# dawa_v4_0.net
KiCad netlist of a schematic drawn in EAGLE
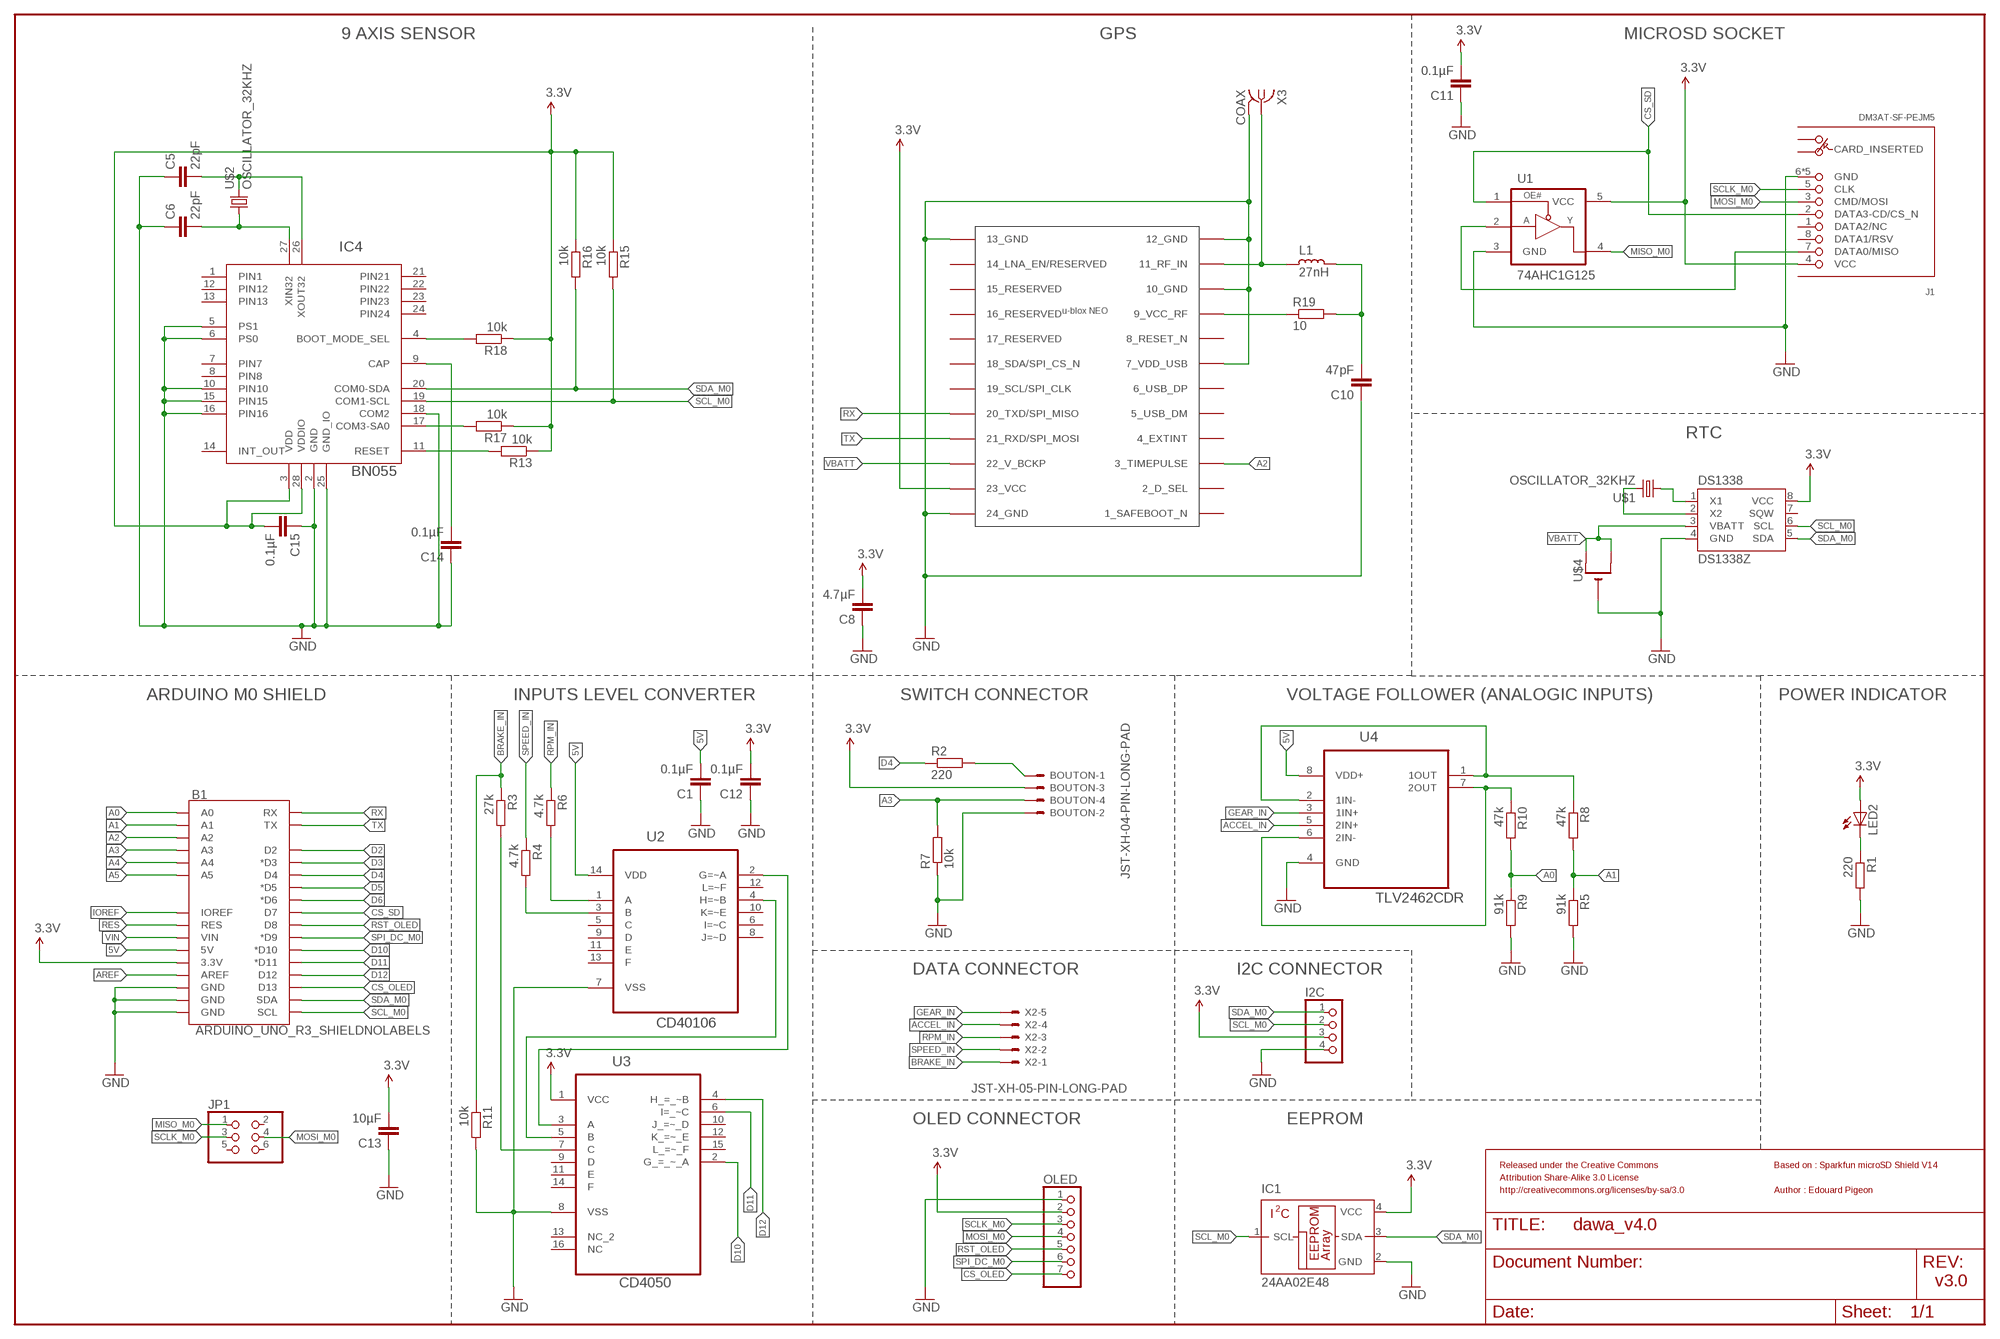
[diagram p0: schematic, sheet 1]

(export (version "E")
  (design (tool "Eeschema 10.0.6"))
  (components
    (comp (ref "B1")
      (value "ARDUINO_UNO_R3_SHIELDNOLABELS")
      (footprint "eagle-import:UNO_R3_SHIELD_NOLABELS")
      (libsource (lib "eagle-import") (part "ARDUINO_UNO_R3_SHIELDNOLABELS"))
    )
    (comp (ref "BOUTON")
      (value "JST-XH-04-PIN-LONG-PAD")
      (footprint "eagle-import:JST-XH-04-PACKAGE-LONG-PAD")
      (libsource (lib "eagle-import") (part "JST-XH-04-PIN-LONG-PAD"))
    )
    (comp (ref "C1")
      (value "0.1µF")
      (footprint "eagle-import:C0603")
      (libsource (lib "eagle-import") (part "C-EUC0603"))
    )
    (comp (ref "C5")
      (value "22pF")
      (footprint "eagle-import:C0603")
      (libsource (lib "eagle-import") (part "C-EUC0603"))
    )
    (comp (ref "C6")
      (value "22pF")
      (footprint "eagle-import:C0603")
      (libsource (lib "eagle-import") (part "C-EUC0603"))
    )
    (comp (ref "C8")
      (value "4.7µF")
      (footprint "eagle-import:C0603")
      (libsource (lib "eagle-import") (part "C-EUC0603"))
    )
    (comp (ref "C10")
      (value "47pF")
      (footprint "eagle-import:C0603")
      (libsource (lib "eagle-import") (part "C-EUC0603"))
    )
    (comp (ref "C11")
      (value "0.1µF")
      (footprint "eagle-import:C0603")
      (libsource (lib "eagle-import") (part "C-EUC0603"))
    )
    (comp (ref "C12")
      (value "0.1µF")
      (footprint "eagle-import:C0603")
      (libsource (lib "eagle-import") (part "C-EUC0603"))
    )
    (comp (ref "C13")
      (value "10µF")
      (footprint "eagle-import:C0603")
      (libsource (lib "eagle-import") (part "C-EUC0603"))
    )
    (comp (ref "C14")
      (value "0.1µF")
      (footprint "eagle-import:C0603")
      (libsource (lib "eagle-import") (part "C-EUC0603"))
    )
    (comp (ref "C15")
      (value "0.1µF")
      (footprint "eagle-import:C0603")
      (libsource (lib "eagle-import") (part "C-EUC0603"))
    )
    (comp (ref "DS1338")
      (value "DS1338Z")
      (footprint "eagle-import:SO08")
      (libsource (lib "eagle-import") (part "DS1338Z"))
    )
    (comp (ref "I2C")
      (value "PINHD-1X4")
      (footprint "eagle-import:1X04")
      (libsource (lib "eagle-import") (part "PINHD-1X4"))
    )
    (comp (ref "IC1")
      (value "24AA02E48")
      (footprint "eagle-import:SOT23-5L")
      (fields (field (name "MF") "MICROCHIP") (field (name "MPN") "24AA00T-I/OTG"))
      (libsource (lib "eagle-import") (part "2400OTAA"))
    )
    (comp (ref "IC4")
      (value "BN055")
      (footprint "eagle-import:LGA-28_3.80X5.20_0.5")
      (fields (field (name "PART_NUMBER") "BNO055"))
      (libsource (lib "eagle-import") (part "1658_BNO055"))
    )
    (comp (ref "J1")
      (value "DM3AT-SF-PEJM5")
      (footprint "eagle-import:DM3AT-SF-PEJM5")
      (libsource (lib "eagle-import") (part "DM3AT-SF-PEJM5"))
    )
    (comp (ref "JP1")
      (value "PINHD-2X3")
      (footprint "eagle-import:2X03")
      (libsource (lib "eagle-import") (part "PINHD-2X3"))
    )
    (comp (ref "L1")
      (value "27nH")
      (footprint "eagle-import:L0603")
      (libsource (lib "eagle-import") (part "L_0603"))
    )
    (comp (ref "LED2")
      (value "LEDCHIPLED_1206")
      (footprint "eagle-import:CHIPLED_1206")
      (libsource (lib "eagle-import") (part "LEDCHIPLED_1206"))
    )
    (comp (ref "OLED")
      (value "PINHD-1X7")
      (footprint "eagle-import:1X07")
      (libsource (lib "eagle-import") (part "PINHD-1X7"))
    )
    (comp (ref "R1")
      (value "220")
      (footprint "eagle-import:R0603")
      (libsource (lib "eagle-import") (part "R-EU_R0603"))
    )
    (comp (ref "R2")
      (value "220")
      (footprint "eagle-import:R0603")
      (libsource (lib "eagle-import") (part "R-EU_R0603"))
    )
    (comp (ref "R3")
      (value "27k")
      (footprint "eagle-import:R0603")
      (libsource (lib "eagle-import") (part "R-EU_R0603"))
    )
    (comp (ref "R4")
      (value "4.7k")
      (footprint "eagle-import:R0603")
      (libsource (lib "eagle-import") (part "R-EU_R0603"))
    )
    (comp (ref "R5")
      (value "91k")
      (footprint "eagle-import:R0603")
      (libsource (lib "eagle-import") (part "R-EU_R0603"))
    )
    (comp (ref "R6")
      (value "4.7k")
      (footprint "eagle-import:R0603")
      (libsource (lib "eagle-import") (part "R-EU_R0603"))
    )
    (comp (ref "R7")
      (value "10k")
      (footprint "eagle-import:R0603")
      (libsource (lib "eagle-import") (part "R-EU_R0603"))
    )
    (comp (ref "R8")
      (value "47k")
      (footprint "eagle-import:R0603")
      (libsource (lib "eagle-import") (part "R-EU_R0603"))
    )
    (comp (ref "R9")
      (value "91k")
      (footprint "eagle-import:R0603")
      (libsource (lib "eagle-import") (part "R-EU_R0603"))
    )
    (comp (ref "R10")
      (value "47k")
      (footprint "eagle-import:R0603")
      (libsource (lib "eagle-import") (part "R-EU_R0603"))
    )
    (comp (ref "R11")
      (value "10k")
      (footprint "eagle-import:R0603")
      (libsource (lib "eagle-import") (part "R-EU_R0603"))
    )
    (comp (ref "R13")
      (value "10k")
      (footprint "eagle-import:R0603")
      (libsource (lib "eagle-import") (part "R-EU_R0603"))
    )
    (comp (ref "R15")
      (value "10k")
      (footprint "eagle-import:R0603")
      (libsource (lib "eagle-import") (part "R-EU_R0603"))
    )
    (comp (ref "R16")
      (value "10k")
      (footprint "eagle-import:R0603")
      (libsource (lib "eagle-import") (part "R-EU_R0603"))
    )
    (comp (ref "R17")
      (value "10k")
      (footprint "eagle-import:R0603")
      (libsource (lib "eagle-import") (part "R-EU_R0603"))
    )
    (comp (ref "R18")
      (value "10k")
      (footprint "eagle-import:R0603")
      (libsource (lib "eagle-import") (part "R-EU_R0603"))
    )
    (comp (ref "R19")
      (value "10")
      (footprint "eagle-import:M1206")
      (libsource (lib "eagle-import") (part "R-EU_M1206"))
    )
    (comp (ref "U$1")
      (value "OSCILLATOR_32KHZ")
      (footprint "eagle-import:OSCILLATOR_SMD")
      (libsource (lib "eagle-import") (part "OSCILLATOR_32KHZ"))
    )
    (comp (ref "U$2")
      (value "OSCILLATOR_32KHZ")
      (footprint "eagle-import:OSCILLATOR_SMD")
      (libsource (lib "eagle-import") (part "OSCILLATOR_32KHZ"))
    )
    (comp (ref "U$3")
      (value "NEO-M8")
      (footprint "eagle-import:NEO-M8")
      (libsource (lib "eagle-import") (part "NEO-M8"))
    )
    (comp (ref "U$4")
      (value "CR1220SMT")
      (footprint "eagle-import:CR1220-SMD")
      (libsource (lib "eagle-import") (part "CR1220SMT"))
    )
    (comp (ref "U1")
      (value "74AHC1G125")
      (footprint "eagle-import:SOT23-5")
      (libsource (lib "eagle-import") (part "74AHC1G125DBV"))
    )
    (comp (ref "U2")
      (value "CD40106")
      (footprint "eagle-import:SOP65P640X120-14N")
      (fields (field (name "MPN") "CD40106BPW"))
      (libsource (lib "eagle-import") (part "CD40106BPW"))
    )
    (comp (ref "U3")
      (value "CD4050")
      (footprint "eagle-import:SOP65P640X120-16N")
      (fields (field (name "MPN") "CD4049UBPW"))
      (libsource (lib "eagle-import") (part "CD4049UBPW"))
    )
    (comp (ref "U4")
      (value "TLV2462CDR")
      (footprint "eagle-import:SOIC127P600X175-8N")
      (libsource (lib "eagle-import") (part "TLV2462CDR"))
    )
    (comp (ref "X2")
      (value "JST-XH-05-PIN-LONG-PAD")
      (footprint "eagle-import:JST-XH-05-PACKAGE-LONG-PAD")
      (libsource (lib "eagle-import") (part "JST-XH-05-PIN-LONG-PAD"))
    )
    (comp (ref "X3")
      (value "COAX")
      (footprint "eagle-import:MMCX-J-P-X-ST-EM1-MKT")
      (libsource (lib "eagle-import") (part "COAX"))
    )
  )
  (nets
    (net (code "1") (name "3.3V") (class "Default")
      (node (ref "B1") (pin "3.3V") (pinfunction "3.3V_3.3V") (pintype "bidirectional"))
      (node (ref "BOUTON") (pin "3") (pinfunction "S_3") (pintype "passive"))
      (node (ref "C11") (pin "2") (pinfunction "2_2") (pintype "passive"))
      (node (ref "C12") (pin "2") (pinfunction "2_2") (pintype "passive"))
      (node (ref "C13") (pin "2") (pinfunction "2_2") (pintype "passive"))
      (node (ref "C15") (pin "2") (pinfunction "2_2") (pintype "passive"))
      (node (ref "C8") (pin "2") (pinfunction "2_2") (pintype "passive"))
      (node (ref "DS1338") (pin "8") (pinfunction "VCC_8") (pintype "bidirectional"))
      (node (ref "I2C") (pin "3") (pinfunction "3_3") (pintype "passive"))
      (node (ref "IC1") (pin "4") (pinfunction "VCC_4") (pintype "power_in"))
      (node (ref "IC4") (pin "28") (pinfunction "VDDIO_28") (pintype "power_in"))
      (node (ref "IC4") (pin "3") (pinfunction "VDD_3") (pintype "power_in"))
      (node (ref "J1") (pin "4") (pinfunction "VCC_4") (pintype "bidirectional"))
      (node (ref "LED2") (pin "A") (pinfunction "A_A") (pintype "passive"))
      (node (ref "OLED") (pin "2") (pinfunction "2_2") (pintype "passive"))
      (node (ref "R13") (pin "1") (pinfunction "1_1") (pintype "passive"))
      (node (ref "R15") (pin "1") (pinfunction "1_1") (pintype "passive"))
      (node (ref "R16") (pin "1") (pinfunction "1_1") (pintype "passive"))
      (node (ref "R17") (pin "1") (pinfunction "1_1") (pintype "passive"))
      (node (ref "R18") (pin "1") (pinfunction "1_1") (pintype "passive"))
      (node (ref "U$3") (pin "23") (pinfunction "23_VCC_23") (pintype "bidirectional"))
      (node (ref "U1") (pin "5") (pinfunction "VCC_5") (pintype "power_in"))
      (node (ref "U3") (pin "1") (pinfunction "VCC_1") (pintype "power_in"))
    )
    (net (code "2") (name "5V") (class "Default")
      (node (ref "B1") (pin "5V") (pinfunction "5V_5V") (pintype "bidirectional"))
      (node (ref "C1") (pin "2") (pinfunction "2_2") (pintype "passive"))
      (node (ref "U2") (pin "14") (pinfunction "VDD_14") (pintype "power_in"))
      (node (ref "U4") (pin "8") (pinfunction "VDD+_8") (pintype "power_in"))
    )
    (net (code "3") (name "A0") (class "Default")
      (node (ref "B1") (pin "A0") (pinfunction "A0_A0") (pintype "bidirectional"))
      (node (ref "R10") (pin "2") (pinfunction "2_2") (pintype "passive"))
      (node (ref "R9") (pin "1") (pinfunction "1_1") (pintype "passive"))
    )
    (net (code "4") (name "A1") (class "Default")
      (node (ref "B1") (pin "A1") (pinfunction "A1_A1") (pintype "bidirectional"))
      (node (ref "R5") (pin "1") (pinfunction "1_1") (pintype "passive"))
      (node (ref "R8") (pin "2") (pinfunction "2_2") (pintype "passive"))
    )
    (net (code "5") (name "A2") (class "Default")
      (node (ref "B1") (pin "A2") (pinfunction "A2_A2") (pintype "bidirectional"))
      (node (ref "U$3") (pin "3") (pinfunction "3_TIMEPULSE_3") (pintype "bidirectional"))
    )
    (net (code "6") (name "A3") (class "Default")
      (node (ref "B1") (pin "A3") (pinfunction "A3_A3") (pintype "bidirectional"))
      (node (ref "BOUTON") (pin "4") (pinfunction "S_4") (pintype "passive"))
      (node (ref "R7") (pin "2") (pinfunction "2_2") (pintype "passive"))
    )
    (net (code "7") (name "A4") (class "Default")
      (node (ref "B1") (pin "A4") (pinfunction "A4_A4") (pintype "bidirectional"))
    )
    (net (code "8") (name "A5") (class "Default")
      (node (ref "B1") (pin "A5") (pinfunction "A5_A5") (pintype "bidirectional"))
    )
    (net (code "9") (name "ACCEL_IN") (class "Default")
      (node (ref "U4") (pin "5") (pinfunction "2IN+_5") (pintype "input"))
      (node (ref "X2") (pin "4") (pinfunction "S_4") (pintype "passive"))
    )
    (net (code "10") (name "AREF") (class "Default")
      (node (ref "B1") (pin "AREF") (pinfunction "AREF_AREF") (pintype "bidirectional"))
    )
    (net (code "11") (name "BRAKE_IN") (class "Default")
      (node (ref "R11") (pin "1") (pinfunction "1_1") (pintype "passive"))
      (node (ref "R3") (pin "1") (pinfunction "1_1") (pintype "passive"))
      (node (ref "X2") (pin "1") (pinfunction "S_1") (pintype "passive"))
    )
    (net (code "12") (name "CS_OLED") (class "Default")
      (node (ref "B1") (pin "D13") (pinfunction "D13_D13") (pintype "bidirectional"))
      (node (ref "OLED") (pin "7") (pinfunction "7_7") (pintype "passive"))
    )
    (net (code "13") (name "CS_SD") (class "Default")
      (node (ref "B1") (pin "D7") (pinfunction "D7_D7") (pintype "bidirectional"))
      (node (ref "J1") (pin "2") (pinfunction "DATA3-CD/CS_N_2") (pintype "bidirectional"))
      (node (ref "U1") (pin "1") (pinfunction "OE#_1") (pintype "input"))
    )
    (net (code "14") (name "D2") (class "Default")
      (node (ref "B1") (pin "D2") (pinfunction "D2_D2") (pintype "bidirectional"))
    )
    (net (code "15") (name "D3") (class "Default")
      (node (ref "B1") (pin "D3") (pinfunction "*D3_D3") (pintype "bidirectional"))
    )
    (net (code "16") (name "D4") (class "Default")
      (node (ref "B1") (pin "D4") (pinfunction "D4_D4") (pintype "bidirectional"))
      (node (ref "R2") (pin "1") (pinfunction "1_1") (pintype "passive"))
    )
    (net (code "17") (name "D5") (class "Default")
      (node (ref "B1") (pin "D5") (pinfunction "*D5_D5") (pintype "bidirectional"))
    )
    (net (code "18") (name "D6") (class "Default")
      (node (ref "B1") (pin "D6") (pinfunction "*D6_D6") (pintype "bidirectional"))
    )
    (net (code "19") (name "D10") (class "Default")
      (node (ref "B1") (pin "D10") (pinfunction "*D10_D10") (pintype "bidirectional"))
      (node (ref "U3") (pin "2") (pinfunction "G_=_~{_A}_2") (pintype "output"))
    )
    (net (code "20") (name "D11") (class "Default")
      (node (ref "B1") (pin "D11") (pinfunction "*D11_D11") (pintype "bidirectional"))
      (node (ref "U3") (pin "6") (pinfunction "I=_~{C}_6") (pintype "output"))
    )
    (net (code "21") (name "D12") (class "Default")
      (node (ref "B1") (pin "D12") (pinfunction "D12_D12") (pintype "bidirectional"))
      (node (ref "U3") (pin "4") (pinfunction "H_=_~{B}_4") (pintype "output"))
    )
    (net (code "22") (name "GEAR_IN") (class "Default")
      (node (ref "U4") (pin "3") (pinfunction "1IN+_3") (pintype "input"))
      (node (ref "X2") (pin "5") (pinfunction "S_5") (pintype "passive"))
    )
    (net (code "23") (name "GND") (class "Default")
      (node (ref "B1") (pin "GND@0") (pinfunction "GND_GND@0") (pintype "bidirectional"))
      (node (ref "B1") (pin "GND@1") (pinfunction "GND_GND@1") (pintype "bidirectional"))
      (node (ref "B1") (pin "GND@2") (pinfunction "GND_GND@2") (pintype "bidirectional"))
      (node (ref "BOUTON") (pin "2") (pinfunction "S_2") (pintype "passive"))
      (node (ref "C1") (pin "1") (pinfunction "1_1") (pintype "passive"))
      (node (ref "C10") (pin "1") (pinfunction "1_1") (pintype "passive"))
      (node (ref "C11") (pin "1") (pinfunction "1_1") (pintype "passive"))
      (node (ref "C12") (pin "1") (pinfunction "1_1") (pintype "passive"))
      (node (ref "C13") (pin "1") (pinfunction "1_1") (pintype "passive"))
      (node (ref "C14") (pin "1") (pinfunction "1_1") (pintype "passive"))
      (node (ref "C15") (pin "1") (pinfunction "1_1") (pintype "passive"))
      (node (ref "C5") (pin "1") (pinfunction "1_1") (pintype "passive"))
      (node (ref "C6") (pin "1") (pinfunction "1_1") (pintype "passive"))
      (node (ref "C8") (pin "1") (pinfunction "1_1") (pintype "passive"))
      (node (ref "DS1338") (pin "4") (pinfunction "GND_4") (pintype "bidirectional"))
      (node (ref "I2C") (pin "4") (pinfunction "4_4") (pintype "passive"))
      (node (ref "IC1") (pin "2") (pinfunction "GND_2") (pintype "power_in"))
      (node (ref "IC4") (pin "10") (pinfunction "PIN10_10") (pintype "passive"))
      (node (ref "IC4") (pin "15") (pinfunction "PIN15_15") (pintype "passive"))
      (node (ref "IC4") (pin "16") (pinfunction "PIN16_16") (pintype "passive"))
      (node (ref "IC4") (pin "18") (pinfunction "COM2_18") (pintype "bidirectional"))
      (node (ref "IC4") (pin "2") (pinfunction "GND_2") (pintype "power_in"))
      (node (ref "IC4") (pin "25") (pinfunction "GND_IO_25") (pintype "power_in"))
      (node (ref "IC4") (pin "5") (pinfunction "PS1_5") (pintype "input"))
      (node (ref "IC4") (pin "6") (pinfunction "PS0_6") (pintype "input"))
      (node (ref "J1") (pin "6") (pinfunction "GND_6") (pintype "bidirectional"))
      (node (ref "J1") (pin "MOUNT0") (pinfunction "GND_MOUNT0") (pintype "bidirectional"))
      (node (ref "J1") (pin "MOUNT1") (pinfunction "GND_MOUNT1") (pintype "bidirectional"))
      (node (ref "J1") (pin "MOUNT2") (pinfunction "GND_MOUNT2") (pintype "bidirectional"))
      (node (ref "J1") (pin "MOUNT3") (pinfunction "GND_MOUNT3") (pintype "bidirectional"))
      (node (ref "OLED") (pin "1") (pinfunction "1_1") (pintype "passive"))
      (node (ref "R1") (pin "2") (pinfunction "2_2") (pintype "passive"))
      (node (ref "R11") (pin "2") (pinfunction "2_2") (pintype "passive"))
      (node (ref "R5") (pin "2") (pinfunction "2_2") (pintype "passive"))
      (node (ref "R7") (pin "1") (pinfunction "1_1") (pintype "passive"))
      (node (ref "R9") (pin "2") (pinfunction "2_2") (pintype "passive"))
      (node (ref "U$3") (pin "10") (pinfunction "10_GND_10") (pintype "bidirectional"))
      (node (ref "U$3") (pin "12") (pinfunction "12_GND_12") (pintype "bidirectional"))
      (node (ref "U$3") (pin "13") (pinfunction "13_GND_13") (pintype "bidirectional"))
      (node (ref "U$3") (pin "24") (pinfunction "24_GND_24") (pintype "bidirectional"))
      (node (ref "U$3") (pin "7") (pinfunction "7_VDD_USB_7") (pintype "bidirectional"))
      (node (ref "U$4") (pin "-") (pinfunction "-_-") (pintype "passive"))
      (node (ref "U1") (pin "3") (pinfunction "GND_3") (pintype "power_in"))
      (node (ref "U2") (pin "7") (pinfunction "VSS_7") (pintype "power_in"))
      (node (ref "U3") (pin "8") (pinfunction "VSS_8") (pintype "power_in"))
      (node (ref "U4") (pin "4") (pinfunction "GND_4") (pintype "passive"))
      (node (ref "X3") (pin "2@1") (pinfunction "GND_2@1") (pintype "power_in"))
    )
    (net (code "24") (name "IOREF") (class "Default")
      (node (ref "B1") (pin "IOREF") (pinfunction "IOREF_IOREF") (pintype "bidirectional"))
    )
    (net (code "25") (name "MISO_M0") (class "Default")
      (node (ref "JP1") (pin "1") (pinfunction "1_1") (pintype "passive"))
      (node (ref "U1") (pin "4") (pinfunction "Y_4") (pintype "output"))
    )
    (net (code "26") (name "MOSI_M0") (class "Default")
      (node (ref "J1") (pin "3") (pinfunction "CMD/MOSI_3") (pintype "bidirectional"))
      (node (ref "JP1") (pin "4") (pinfunction "4_4") (pintype "passive"))
      (node (ref "OLED") (pin "4") (pinfunction "4_4") (pintype "passive"))
    )
    (net (code "27") (name "Net-(BOUTONA-S)") (class "Default")
      (node (ref "BOUTON") (pin "1") (pinfunction "S_1") (pintype "passive"))
      (node (ref "R2") (pin "2") (pinfunction "2_2") (pintype "passive"))
    )
    (net (code "28") (name "Net-(C10-Pad2)") (class "Default")
      (node (ref "C10") (pin "2") (pinfunction "2_2") (pintype "passive"))
      (node (ref "L1") (pin "1") (pinfunction "1_1") (pintype "passive"))
      (node (ref "R19") (pin "2") (pinfunction "2_2") (pintype "passive"))
    )
    (net (code "29") (name "Net-(DS1338-X1)") (class "Default")
      (node (ref "DS1338") (pin "1") (pinfunction "X1_1") (pintype "bidirectional"))
      (node (ref "U$1") (pin "1") (pinfunction "1_1") (pintype "passive"))
    )
    (net (code "30") (name "Net-(DS1338-X2)") (class "Default")
      (node (ref "DS1338") (pin "2") (pinfunction "X2_2") (pintype "bidirectional"))
      (node (ref "U$1") (pin "2") (pinfunction "2_2") (pintype "passive"))
    )
    (net (code "31") (name "Net-(IC4-BOOT_MODE_SEL)") (class "Default")
      (node (ref "IC4") (pin "4") (pinfunction "BOOT_MODE_SEL_4") (pintype "input"))
      (node (ref "R18") (pin "2") (pinfunction "2_2") (pintype "passive"))
    )
    (net (code "32") (name "Net-(IC4-CAP)") (class "Default")
      (node (ref "C14") (pin "2") (pinfunction "2_2") (pintype "passive"))
      (node (ref "IC4") (pin "9") (pinfunction "CAP_9") (pintype "tri_state"))
    )
    (net (code "33") (name "Net-(IC4-COM3-SA0)") (class "Default")
      (node (ref "IC4") (pin "17") (pinfunction "COM3-SA0_17") (pintype "bidirectional"))
      (node (ref "R17") (pin "2") (pinfunction "2_2") (pintype "passive"))
    )
    (net (code "34") (name "Net-(IC4-RESET)") (class "Default")
      (node (ref "IC4") (pin "11") (pinfunction "RESET_11") (pintype "input"))
      (node (ref "R13") (pin "2") (pinfunction "2_2") (pintype "passive"))
    )
    (net (code "35") (name "Net-(IC4-XIN32)") (class "Default")
      (node (ref "C6") (pin "2") (pinfunction "2_2") (pintype "passive"))
      (node (ref "IC4") (pin "27") (pinfunction "XIN32_27") (pintype "bidirectional"))
      (node (ref "U$2") (pin "1") (pinfunction "1_1") (pintype "passive"))
    )
    (net (code "36") (name "Net-(IC4-XOUT32)") (class "Default")
      (node (ref "C5") (pin "2") (pinfunction "2_2") (pintype "passive"))
      (node (ref "IC4") (pin "26") (pinfunction "XOUT32_26") (pintype "output"))
      (node (ref "U$2") (pin "2") (pinfunction "2_2") (pintype "passive"))
    )
    (net (code "37") (name "Net-(J1-DATA0{slash}MISO)") (class "Default")
      (node (ref "J1") (pin "7") (pinfunction "DATA0/MISO_7") (pintype "bidirectional"))
      (node (ref "U1") (pin "2") (pinfunction "A_2") (pintype "input"))
    )
    (net (code "38") (name "Net-(LED2-PadC)") (class "Default")
      (node (ref "LED2") (pin "C") (pinfunction "C_C") (pintype "passive"))
      (node (ref "R1") (pin "1") (pinfunction "1_1") (pintype "passive"))
    )
    (net (code "39") (name "Net-(U$3-9_VCC_RF)") (class "Default")
      (node (ref "R19") (pin "1") (pinfunction "1_1") (pintype "passive"))
      (node (ref "U$3") (pin "9") (pinfunction "9_VCC_RF_9") (pintype "bidirectional"))
    )
    (net (code "40") (name "Net-(U$3-11_RF_IN)") (class "Default")
      (node (ref "L1") (pin "2") (pinfunction "2_2") (pintype "passive"))
      (node (ref "U$3") (pin "11") (pinfunction "11_RF_IN_11") (pintype "bidirectional"))
      (node (ref "X3") (pin "1") (pinfunction "1_1") (pintype "passive"))
    )
    (net (code "41") (name "Net-(U2-A)") (class "Default")
      (node (ref "R6") (pin "2") (pinfunction "2_2") (pintype "passive"))
      (node (ref "U2") (pin "1") (pinfunction "A_1") (pintype "input"))
    )
    (net (code "42") (name "Net-(U2-B)") (class "Default")
      (node (ref "R4") (pin "2") (pinfunction "2_2") (pintype "passive"))
      (node (ref "U2") (pin "3") (pinfunction "B_3") (pintype "input"))
    )
    (net (code "43") (name "Net-(U2-G=~{A})") (class "Default")
      (node (ref "U2") (pin "2") (pinfunction "G=~{A}_2") (pintype "output"))
      (node (ref "U3") (pin "3") (pinfunction "A_3") (pintype "input"))
    )
    (net (code "44") (name "Net-(U2-H=~{B})") (class "Default")
      (node (ref "U2") (pin "4") (pinfunction "H=~{B}_4") (pintype "output"))
      (node (ref "U3") (pin "5") (pinfunction "B_5") (pintype "input"))
    )
    (net (code "45") (name "Net-(U3-C)") (class "Default")
      (node (ref "R3") (pin "2") (pinfunction "2_2") (pintype "passive"))
      (node (ref "U3") (pin "7") (pinfunction "C_7") (pintype "input"))
    )
    (net (code "46") (name "Net-(U4-1IN-)") (class "Default")
      (node (ref "R8") (pin "1") (pinfunction "1_1") (pintype "passive"))
      (node (ref "U4") (pin "1") (pinfunction "1OUT_1") (pintype "output"))
      (node (ref "U4") (pin "2") (pinfunction "1IN-_2") (pintype "input"))
    )
    (net (code "47") (name "Net-(U4-2IN-)") (class "Default")
      (node (ref "R10") (pin "1") (pinfunction "1_1") (pintype "passive"))
      (node (ref "U4") (pin "6") (pinfunction "2IN-_6") (pintype "input"))
      (node (ref "U4") (pin "7") (pinfunction "2OUT_7") (pintype "output"))
    )
    (net (code "48") (name "RES") (class "Default")
      (node (ref "B1") (pin "RES") (pinfunction "RES_RES") (pintype "bidirectional"))
    )
    (net (code "49") (name "RPM_IN") (class "Default")
      (node (ref "R6") (pin "1") (pinfunction "1_1") (pintype "passive"))
      (node (ref "X2") (pin "3") (pinfunction "S_3") (pintype "passive"))
    )
    (net (code "50") (name "RST_OLED") (class "Default")
      (node (ref "B1") (pin "D8") (pinfunction "D8_D8") (pintype "bidirectional"))
      (node (ref "OLED") (pin "5") (pinfunction "5_5") (pintype "passive"))
    )
    (net (code "51") (name "RX") (class "Default")
      (node (ref "B1") (pin "RX") (pinfunction "RX_RX") (pintype "bidirectional"))
      (node (ref "U$3") (pin "20") (pinfunction "20_TXD/SPI_MISO_20") (pintype "bidirectional"))
    )
    (net (code "52") (name "SCLK_M0") (class "Default")
      (node (ref "J1") (pin "5") (pinfunction "CLK_5") (pintype "bidirectional"))
      (node (ref "JP1") (pin "3") (pinfunction "3_3") (pintype "passive"))
      (node (ref "OLED") (pin "3") (pinfunction "3_3") (pintype "passive"))
    )
    (net (code "53") (name "SCL_M0") (class "Default")
      (node (ref "B1") (pin "SCL") (pinfunction "SCL_SCL") (pintype "bidirectional"))
      (node (ref "DS1338") (pin "6") (pinfunction "SCL_6") (pintype "bidirectional"))
      (node (ref "I2C") (pin "2") (pinfunction "2_2") (pintype "passive"))
      (node (ref "IC1") (pin "1") (pinfunction "SCL_1") (pintype "input"))
      (node (ref "IC4") (pin "19") (pinfunction "COM1-SCL_19") (pintype "bidirectional"))
      (node (ref "R15") (pin "2") (pinfunction "2_2") (pintype "passive"))
    )
    (net (code "54") (name "SDA_M0") (class "Default")
      (node (ref "B1") (pin "SDA") (pinfunction "SDA_SDA") (pintype "bidirectional"))
      (node (ref "DS1338") (pin "5") (pinfunction "SDA_5") (pintype "bidirectional"))
      (node (ref "I2C") (pin "1") (pinfunction "1_1") (pintype "passive"))
      (node (ref "IC1") (pin "3") (pinfunction "SDA_3") (pintype "bidirectional"))
      (node (ref "IC4") (pin "20") (pinfunction "COM0-SDA_20") (pintype "bidirectional"))
      (node (ref "R16") (pin "2") (pinfunction "2_2") (pintype "passive"))
    )
    (net (code "55") (name "SPEED_IN") (class "Default")
      (node (ref "R4") (pin "1") (pinfunction "1_1") (pintype "passive"))
      (node (ref "X2") (pin "2") (pinfunction "S_2") (pintype "passive"))
    )
    (net (code "56") (name "SPI_DC_M0") (class "Default")
      (node (ref "B1") (pin "D9") (pinfunction "*D9_D9") (pintype "bidirectional"))
      (node (ref "OLED") (pin "6") (pinfunction "6_6") (pintype "passive"))
    )
    (net (code "57") (name "TX") (class "Default")
      (node (ref "B1") (pin "TX") (pinfunction "TX_TX") (pintype "bidirectional"))
      (node (ref "U$3") (pin "21") (pinfunction "21_RXD/SPI_MOSI_21") (pintype "bidirectional"))
    )
    (net (code "58") (name "VBATT") (class "Default")
      (node (ref "DS1338") (pin "3") (pinfunction "VBATT_3") (pintype "bidirectional"))
      (node (ref "U$3") (pin "22") (pinfunction "22_V_BCKP_22") (pintype "bidirectional"))
      (node (ref "U$4") (pin "+$1") (pinfunction "+_+$1") (pintype "passive"))
      (node (ref "U$4") (pin "+$2") (pinfunction "+1_+$2") (pintype "passive"))
    )
    (net (code "59") (name "VIN") (class "Default")
      (node (ref "B1") (pin "VIN") (pinfunction "VIN_VIN") (pintype "bidirectional"))
    )
    (net (code "60") (name "unconnected-(DS1338-SQW-Pad7)") (class "Default")
      (node (ref "DS1338") (pin "7") (pinfunction "SQW_7") (pintype "bidirectional"))
    )
    (net (code "61") (name "unconnected-(IC4-INT_OUT-Pad14)") (class "Default")
      (node (ref "IC4") (pin "14") (pinfunction "INT_OUT_14") (pintype "output"))
    )
    (net (code "62") (name "unconnected-(IC4-PIN1-Pad1)") (class "Default")
      (node (ref "IC4") (pin "1") (pinfunction "PIN1_1") (pintype "no_connect"))
    )
    (net (code "63") (name "unconnected-(IC4-PIN7-Pad7)") (class "Default")
      (node (ref "IC4") (pin "7") (pinfunction "PIN7_7") (pintype "tri_state"))
    )
    (net (code "64") (name "unconnected-(IC4-PIN8-Pad8)") (class "Default")
      (node (ref "IC4") (pin "8") (pinfunction "PIN8_8") (pintype "tri_state"))
    )
    (net (code "65") (name "unconnected-(IC4-PIN12-Pad12)") (class "Default")
      (node (ref "IC4") (pin "12") (pinfunction "PIN12_12") (pintype "passive"))
    )
    (net (code "66") (name "unconnected-(IC4-PIN13-Pad13)") (class "Default")
      (node (ref "IC4") (pin "13") (pinfunction "PIN13_13") (pintype "passive"))
    )
    (net (code "67") (name "unconnected-(IC4-PIN21-Pad21)") (class "Default")
      (node (ref "IC4") (pin "21") (pinfunction "PIN21_21") (pintype "passive"))
    )
    (net (code "68") (name "unconnected-(IC4-PIN22-Pad22)") (class "Default")
      (node (ref "IC4") (pin "22") (pinfunction "PIN22_22") (pintype "passive"))
    )
    (net (code "69") (name "unconnected-(IC4-PIN23-Pad23)") (class "Default")
      (node (ref "IC4") (pin "23") (pinfunction "PIN23_23") (pintype "passive"))
    )
    (net (code "70") (name "unconnected-(IC4-PIN24-Pad24)") (class "Default")
      (node (ref "IC4") (pin "24") (pinfunction "PIN24_24") (pintype "passive"))
    )
    (net (code "71") (name "unconnected-(J1-DATA1{slash}RSV-Pad8)") (class "Default")
      (node (ref "J1") (pin "8") (pinfunction "DATA1/RSV_8") (pintype "bidirectional"))
    )
    (net (code "72") (name "unconnected-(J1-DATA2{slash}NC-Pad1)") (class "Default")
      (node (ref "J1") (pin "1") (pinfunction "DATA2/NC_1") (pintype "bidirectional"))
    )
    (net (code "73") (name "unconnected-(J1-PadA)") (class "Default")
      (node (ref "J1") (pin "A") (pinfunction "A_A") (pintype "bidirectional"))
    )
    (net (code "74") (name "unconnected-(J1-PadB)") (class "Default")
      (node (ref "J1") (pin "B") (pinfunction "B_B") (pintype "bidirectional"))
    )
    (net (code "75") (name "unconnected-(JP1-Pad2)") (class "Default")
      (node (ref "JP1") (pin "2") (pinfunction "2_2") (pintype "passive"))
    )
    (net (code "76") (name "unconnected-(JP1-Pad5)") (class "Default")
      (node (ref "JP1") (pin "5") (pinfunction "5_5") (pintype "passive"))
    )
    (net (code "77") (name "unconnected-(JP1-Pad6)") (class "Default")
      (node (ref "JP1") (pin "6") (pinfunction "6_6") (pintype "passive"))
    )
    (net (code "78") (name "unconnected-(U$3-1_SAFEBOOT_N-Pad1)") (class "Default")
      (node (ref "U$3") (pin "1") (pinfunction "1_SAFEBOOT_N_1") (pintype "bidirectional"))
    )
    (net (code "79") (name "unconnected-(U$3-2_D_SEL-Pad2)") (class "Default")
      (node (ref "U$3") (pin "2") (pinfunction "2_D_SEL_2") (pintype "bidirectional"))
    )
    (net (code "80") (name "unconnected-(U$3-4_EXTINT-Pad4)") (class "Default")
      (node (ref "U$3") (pin "4") (pinfunction "4_EXTINT_4") (pintype "bidirectional"))
    )
    (net (code "81") (name "unconnected-(U$3-5_USB_DM-Pad5)") (class "Default")
      (node (ref "U$3") (pin "5") (pinfunction "5_USB_DM_5") (pintype "bidirectional"))
    )
    (net (code "82") (name "unconnected-(U$3-6_USB_DP-Pad6)") (class "Default")
      (node (ref "U$3") (pin "6") (pinfunction "6_USB_DP_6") (pintype "bidirectional"))
    )
    (net (code "83") (name "unconnected-(U$3-8_RESET_N-Pad8)") (class "Default")
      (node (ref "U$3") (pin "8") (pinfunction "8_RESET_N_8") (pintype "bidirectional"))
    )
    (net (code "84") (name "unconnected-(U$3-14_LNA_EN{slash}RESERVED-Pad14)") (class "Default")
      (node (ref "U$3") (pin "14") (pinfunction "14_LNA_EN/RESERVED_14") (pintype "bidirectional"))
    )
    (net (code "85") (name "unconnected-(U$3-15_RESERVED-Pad15)") (class "Default")
      (node (ref "U$3") (pin "15") (pinfunction "15_RESERVED_15") (pintype "bidirectional"))
    )
    (net (code "86") (name "unconnected-(U$3-16_RESERVED-Pad16)") (class "Default")
      (node (ref "U$3") (pin "16") (pinfunction "16_RESERVED_16") (pintype "bidirectional"))
    )
    (net (code "87") (name "unconnected-(U$3-17_RESERVED-Pad17)") (class "Default")
      (node (ref "U$3") (pin "17") (pinfunction "17_RESERVED_17") (pintype "bidirectional"))
    )
    (net (code "88") (name "unconnected-(U$3-18_SDA{slash}SPI_CS_N-Pad18)") (class "Default")
      (node (ref "U$3") (pin "18") (pinfunction "18_SDA/SPI_CS_N_18") (pintype "bidirectional"))
    )
    (net (code "89") (name "unconnected-(U$3-19_SCL{slash}SPI_CLK-Pad19)") (class "Default")
      (node (ref "U$3") (pin "19") (pinfunction "19_SCL/SPI_CLK_19") (pintype "bidirectional"))
    )
    (net (code "90") (name "unconnected-(U2-C-Pad5)") (class "Default")
      (node (ref "U2") (pin "5") (pinfunction "C_5") (pintype "input"))
    )
    (net (code "91") (name "unconnected-(U2-D-Pad9)") (class "Default")
      (node (ref "U2") (pin "9") (pinfunction "D_9") (pintype "input"))
    )
    (net (code "92") (name "unconnected-(U2-E-Pad11)") (class "Default")
      (node (ref "U2") (pin "11") (pinfunction "E_11") (pintype "input"))
    )
    (net (code "93") (name "unconnected-(U2-F-Pad13)") (class "Default")
      (node (ref "U2") (pin "13") (pinfunction "F_13") (pintype "input"))
    )
    (net (code "94") (name "unconnected-(U2-I=~{C}-Pad6)") (class "Default")
      (node (ref "U2") (pin "6") (pinfunction "I=~{C}_6") (pintype "output"))
    )
    (net (code "95") (name "unconnected-(U2-J=~{D}-Pad8)") (class "Default")
      (node (ref "U2") (pin "8") (pinfunction "J=~{D}_8") (pintype "output"))
    )
    (net (code "96") (name "unconnected-(U2-K=~{E}-Pad10)") (class "Default")
      (node (ref "U2") (pin "10") (pinfunction "K=~{E}_10") (pintype "output"))
    )
    (net (code "97") (name "unconnected-(U2-L=~{F}-Pad12)") (class "Default")
      (node (ref "U2") (pin "12") (pinfunction "L=~{F}_12") (pintype "output"))
    )
    (net (code "98") (name "unconnected-(U3-D-Pad9)") (class "Default")
      (node (ref "U3") (pin "9") (pinfunction "D_9") (pintype "input"))
    )
    (net (code "99") (name "unconnected-(U3-E-Pad11)") (class "Default")
      (node (ref "U3") (pin "11") (pinfunction "E_11") (pintype "input"))
    )
    (net (code "100") (name "unconnected-(U3-F-Pad14)") (class "Default")
      (node (ref "U3") (pin "14") (pinfunction "F_14") (pintype "input"))
    )
    (net (code "101") (name "unconnected-(U3-J_=~{_D}-Pad10)") (class "Default")
      (node (ref "U3") (pin "10") (pinfunction "J_=~{_D}_10") (pintype "output"))
    )
    (net (code "102") (name "unconnected-(U3-K_=~{_E}-Pad12)") (class "Default")
      (node (ref "U3") (pin "12") (pinfunction "K_=~{_E}_12") (pintype "output"))
    )
    (net (code "103") (name "unconnected-(U3-L_=~{_F}-Pad15)") (class "Default")
      (node (ref "U3") (pin "15") (pinfunction "L_=~{_F}_15") (pintype "output"))
    )
    (net (code "104") (name "unconnected-(U3-NC-Pad16)") (class "Default")
      (node (ref "U3") (pin "16") (pinfunction "NC_16") (pintype "no_connect"))
    )
    (net (code "105") (name "unconnected-(U3-NC_2-Pad13)") (class "Default")
      (node (ref "U3") (pin "13") (pinfunction "NC_2_13") (pintype "no_connect"))
    )
  )
)
